# CAN_I2C.net
KiCad netlist of a schematic drawn in Altium Designer
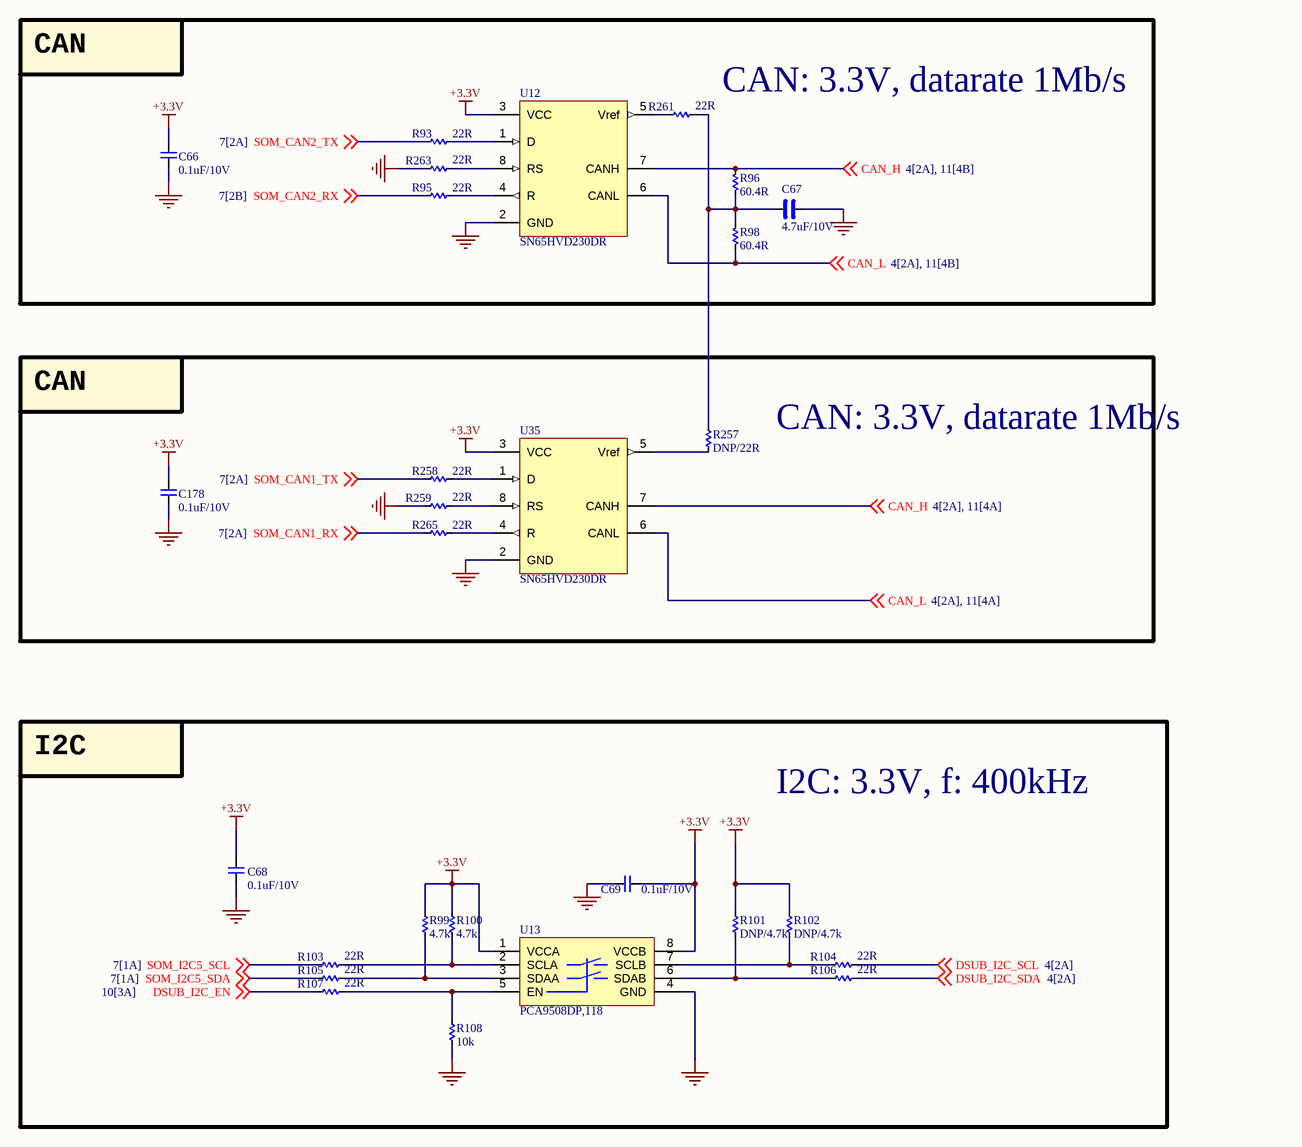
[diagram p0: CAN_I2C.SchDoc]

(export (version "E")
  (design (tool "Eeschema 10.0.6"))
  (components
    (comp (ref "C66")
      (value "0.1uF/10V")
      (footprint "CAP_C_1005X60")
      (description "CAP CHIP")
      (libsource (lib "LABLIB") (part "_CAP_C_2"))
    )
    (comp (ref "C67")
      (value "4.7uF/10V")
      (footprint "CAP_C_1608X80")
      (description "CAP CHIP High Value")
      (libsource (lib "LABLIB") (part "_CAP_C_High_2"))
    )
    (comp (ref "C68")
      (value "0.1uF/10V")
      (footprint "CAP_C_1005X60")
      (description "CAP CHIP")
      (libsource (lib "LABLIB") (part "_CAP_C_2"))
    )
    (comp (ref "C69")
      (value "0.1uF/10V")
      (footprint "CAP_C_1005X60")
      (description "CAP CHIP")
      (libsource (lib "LABLIB") (part "_CAP_C_2"))
    )
    (comp (ref "C178")
      (value "0.1uF/10V")
      (footprint "CAP_C_1005X60")
      (description "CAP CHIP")
      (libsource (lib "LABLIB") (part "_CAP_C_2"))
    )
    (comp (ref "R93")
      (value "22R")
      (footprint "RES_C_1005X40")
      (description "RES")
      (libsource (lib "LABLIB") (part "_RES_B_2"))
    )
    (comp (ref "R95")
      (value "22R")
      (footprint "RES_C_1005X40")
      (description "RES")
      (libsource (lib "LABLIB") (part "_RES_B_2"))
    )
    (comp (ref "R96")
      (value "60.4R")
      (footprint "RES_C_1005X40")
      (description "RES")
      (libsource (lib "LABLIB") (part "_RES_B_2"))
    )
    (comp (ref "R98")
      (value "60.4R")
      (footprint "RES_C_1005X40")
      (description "RES")
      (libsource (lib "LABLIB") (part "_RES_B_2"))
    )
    (comp (ref "R99")
      (value "4.7k")
      (footprint "RES_C_1005X40")
      (description "RES")
      (libsource (lib "LABLIB") (part "_RES_B_2"))
    )
    (comp (ref "R100")
      (value "4.7k")
      (footprint "RES_C_1005X40")
      (description "RES")
      (libsource (lib "LABLIB") (part "_RES_B_2"))
    )
    (comp (ref "R101")
      (value "DNP/4.7k")
      (footprint "RES_C_1005X40")
      (description "RES")
      (libsource (lib "LABLIB") (part "_RES_B_2"))
    )
    (comp (ref "R102")
      (value "DNP/4.7k")
      (footprint "RES_C_1005X40")
      (description "RES")
      (libsource (lib "LABLIB") (part "_RES_B_2"))
    )
    (comp (ref "R103")
      (value "22R")
      (footprint "RES_C_1005X40")
      (description "RES")
      (libsource (lib "LABLIB") (part "_RES_B_2"))
    )
    (comp (ref "R104")
      (value "22R")
      (footprint "RES_C_1005X40")
      (description "RES")
      (libsource (lib "LABLIB") (part "_RES_B_2"))
    )
    (comp (ref "R105")
      (value "22R")
      (footprint "RES_C_1005X40")
      (description "RES")
      (libsource (lib "LABLIB") (part "_RES_B_2"))
    )
    (comp (ref "R106")
      (value "22R")
      (footprint "RES_C_1005X40")
      (description "RES")
      (libsource (lib "LABLIB") (part "_RES_B_2"))
    )
    (comp (ref "R107")
      (value "22R")
      (footprint "RES_C_1005X40")
      (description "RES")
      (libsource (lib "LABLIB") (part "_RES_B_2"))
    )
    (comp (ref "R108")
      (value "10k")
      (footprint "RES_C_1005X40")
      (description "RES")
      (libsource (lib "LABLIB") (part "_RES_B_2"))
    )
    (comp (ref "R257")
      (value "DNP/22R")
      (footprint "RES_C_1005X40")
      (description "RES")
      (libsource (lib "LABLIB") (part "_RES_B_2"))
    )
    (comp (ref "R258")
      (value "22R")
      (footprint "RES_C_1005X40")
      (description "RES")
      (libsource (lib "LABLIB") (part "_RES_B_2"))
    )
    (comp (ref "R259")
      (value "22R")
      (footprint "RES_C_1005X40")
      (description "RES")
      (libsource (lib "LABLIB") (part "_RES_B_2"))
    )
    (comp (ref "R261")
      (value "22R")
      (footprint "RES_C_1005X40")
      (description "RES")
      (libsource (lib "LABLIB") (part "_RES_B_2"))
    )
    (comp (ref "R263")
      (value "22R")
      (footprint "RES_C_1005X40")
      (description "RES")
      (libsource (lib "LABLIB") (part "_RES_B_2"))
    )
    (comp (ref "R265")
      (value "22R")
      (footprint "RES_C_1005X40")
      (description "RES")
      (libsource (lib "LABLIB") (part "_RES_B_2"))
    )
    (comp (ref "U12")
      (value "SN65HVD230DR")
      (footprint "SOIC127P602X173-8N")
      (description "IC TRANSCEIVER HALF 1/1 8SOIC")
      (libsource (lib "LABLIB") (part "IC_CAN_SN65HVD230DR"))
    )
    (comp (ref "U13")
      (value "PCA9508DP,118")
      (footprint "TSOP8")
      (libsource (lib "EXP_HW_V3") (part "PCA9508DP,118"))
    )
    (comp (ref "U35")
      (value "SN65HVD230DR")
      (footprint "SOIC127P602X173-8N")
      (description "IC TRANSCEIVER HALF 1/1 8SOIC")
      (libsource (lib "LABLIB") (part "IC_CAN_SN65HVD230DR"))
    )
  )
  (nets
    (net (code "1") (name "+3.3V") (class "Default")
      (node (ref "C178") (pin "2") (pinfunction "2_2") (pintype "passive"))
      (node (ref "C66") (pin "2") (pinfunction "2_2") (pintype "passive"))
      (node (ref "C68") (pin "2") (pinfunction "2_2") (pintype "passive"))
      (node (ref "C69") (pin "1") (pinfunction "1_1") (pintype "passive"))
      (node (ref "R100") (pin "1") (pinfunction "1_1") (pintype "passive"))
      (node (ref "R101") (pin "1") (pinfunction "1_1") (pintype "passive"))
      (node (ref "R102") (pin "1") (pinfunction "1_1") (pintype "passive"))
      (node (ref "R99") (pin "1") (pinfunction "1_1") (pintype "passive"))
      (node (ref "U12") (pin "3") (pinfunction "VCC_3") (pintype "passive"))
      (node (ref "U13") (pin "1") (pinfunction "VCCA_1") (pintype "passive"))
      (node (ref "U13") (pin "8") (pinfunction "VCCB_8") (pintype "passive"))
      (node (ref "U35") (pin "3") (pinfunction "VCC_3") (pintype "passive"))
    )
    (net (code "2") (name "CAN_H") (class "Default")
      (node (ref "R96") (pin "2") (pinfunction "2_2") (pintype "passive"))
      (node (ref "U12") (pin "7") (pinfunction "CANH_7") (pintype "passive"))
      (node (ref "U35") (pin "7") (pinfunction "CANH_7") (pintype "passive"))
    )
    (net (code "3") (name "CAN_L") (class "Default")
      (node (ref "R98") (pin "1") (pinfunction "1_1") (pintype "passive"))
      (node (ref "U12") (pin "6") (pinfunction "CANL_6") (pintype "passive"))
      (node (ref "U35") (pin "6") (pinfunction "CANL_6") (pintype "passive"))
    )
    (net (code "4") (name "DSUB_I2C_EN") (class "Default")
      (node (ref "R107") (pin "2") (pinfunction "2_2") (pintype "passive"))
    )
    (net (code "5") (name "DSUB_I2C_SCL") (class "Default")
      (node (ref "R104") (pin "1") (pinfunction "1_1") (pintype "passive"))
    )
    (net (code "6") (name "DSUB_I2C_SDA") (class "Default")
      (node (ref "R106") (pin "1") (pinfunction "1_1") (pintype "passive"))
    )
    (net (code "7") (name "GND") (class "Default")
      (node (ref "C178") (pin "1") (pinfunction "1_1") (pintype "passive"))
      (node (ref "C66") (pin "1") (pinfunction "1_1") (pintype "passive"))
      (node (ref "C67") (pin "1") (pinfunction "1_1") (pintype "passive"))
      (node (ref "C68") (pin "1") (pinfunction "1_1") (pintype "passive"))
      (node (ref "C69") (pin "2") (pinfunction "2_2") (pintype "passive"))
      (node (ref "R108") (pin "1") (pinfunction "1_1") (pintype "passive"))
      (node (ref "R259") (pin "2") (pinfunction "2_2") (pintype "passive"))
      (node (ref "R263") (pin "2") (pinfunction "2_2") (pintype "passive"))
      (node (ref "U12") (pin "2") (pinfunction "GND_2") (pintype "passive"))
      (node (ref "U13") (pin "4") (pinfunction "GND_4") (pintype "passive"))
      (node (ref "U35") (pin "2") (pinfunction "GND_2") (pintype "passive"))
    )
    (net (code "8") (name "Net-(C67-Pad2)") (class "Default")
      (node (ref "C67") (pin "2") (pinfunction "2_2") (pintype "passive"))
      (node (ref "R257") (pin "1") (pinfunction "1_1") (pintype "passive"))
      (node (ref "R261") (pin "1") (pinfunction "1_1") (pintype "passive"))
      (node (ref "R96") (pin "1") (pinfunction "1_1") (pintype "passive"))
      (node (ref "R98") (pin "2") (pinfunction "2_2") (pintype "passive"))
    )
    (net (code "9") (name "Net-(U12-D)") (class "Default")
      (node (ref "R93") (pin "2") (pinfunction "2_2") (pintype "passive"))
      (node (ref "U12") (pin "1") (pinfunction "D_1") (pintype "input"))
    )
    (net (code "10") (name "Net-(U12-R)") (class "Default")
      (node (ref "R95") (pin "2") (pinfunction "2_2") (pintype "passive"))
      (node (ref "U12") (pin "4") (pinfunction "R_4") (pintype "output"))
    )
    (net (code "11") (name "Net-(U12-RS)") (class "Default")
      (node (ref "R263") (pin "1") (pinfunction "1_1") (pintype "passive"))
      (node (ref "U12") (pin "8") (pinfunction "RS_8") (pintype "input"))
    )
    (net (code "12") (name "Net-(U12-Vref)") (class "Default")
      (node (ref "R261") (pin "2") (pinfunction "2_2") (pintype "passive"))
      (node (ref "U12") (pin "5") (pinfunction "Vref_5") (pintype "output"))
    )
    (net (code "13") (name "Net-(U13-EN)") (class "Default")
      (node (ref "R107") (pin "1") (pinfunction "1_1") (pintype "passive"))
      (node (ref "R108") (pin "2") (pinfunction "2_2") (pintype "passive"))
      (node (ref "U13") (pin "5") (pinfunction "EN_5") (pintype "passive"))
    )
    (net (code "14") (name "Net-(U13-SCLA)") (class "Default")
      (node (ref "R100") (pin "2") (pinfunction "2_2") (pintype "passive"))
      (node (ref "R103") (pin "1") (pinfunction "1_1") (pintype "passive"))
      (node (ref "U13") (pin "2") (pinfunction "SCLA_2") (pintype "passive"))
    )
    (net (code "15") (name "Net-(U13-SCLB)") (class "Default")
      (node (ref "R102") (pin "2") (pinfunction "2_2") (pintype "passive"))
      (node (ref "R104") (pin "2") (pinfunction "2_2") (pintype "passive"))
      (node (ref "U13") (pin "7") (pinfunction "SCLB_7") (pintype "passive"))
    )
    (net (code "16") (name "Net-(U13-SDAA)") (class "Default")
      (node (ref "R105") (pin "1") (pinfunction "1_1") (pintype "passive"))
      (node (ref "R99") (pin "2") (pinfunction "2_2") (pintype "passive"))
      (node (ref "U13") (pin "3") (pinfunction "SDAA_3") (pintype "passive"))
    )
    (net (code "17") (name "Net-(U13-SDAB)") (class "Default")
      (node (ref "R101") (pin "2") (pinfunction "2_2") (pintype "passive"))
      (node (ref "R106") (pin "2") (pinfunction "2_2") (pintype "passive"))
      (node (ref "U13") (pin "6") (pinfunction "SDAB_6") (pintype "passive"))
    )
    (net (code "18") (name "Net-(U35-D)") (class "Default")
      (node (ref "R258") (pin "2") (pinfunction "2_2") (pintype "passive"))
      (node (ref "U35") (pin "1") (pinfunction "D_1") (pintype "input"))
    )
    (net (code "19") (name "Net-(U35-R)") (class "Default")
      (node (ref "R265") (pin "2") (pinfunction "2_2") (pintype "passive"))
      (node (ref "U35") (pin "4") (pinfunction "R_4") (pintype "output"))
    )
    (net (code "20") (name "Net-(U35-RS)") (class "Default")
      (node (ref "R259") (pin "1") (pinfunction "1_1") (pintype "passive"))
      (node (ref "U35") (pin "8") (pinfunction "RS_8") (pintype "input"))
    )
    (net (code "21") (name "Net-(U35-Vref)") (class "Default")
      (node (ref "R257") (pin "2") (pinfunction "2_2") (pintype "passive"))
      (node (ref "U35") (pin "5") (pinfunction "Vref_5") (pintype "output"))
    )
    (net (code "22") (name "SOM_CAN1_RX") (class "Default")
      (node (ref "R265") (pin "1") (pinfunction "1_1") (pintype "passive"))
    )
    (net (code "23") (name "SOM_CAN1_TX") (class "Default")
      (node (ref "R258") (pin "1") (pinfunction "1_1") (pintype "passive"))
    )
    (net (code "24") (name "SOM_CAN2_RX") (class "Default")
      (node (ref "R95") (pin "1") (pinfunction "1_1") (pintype "passive"))
    )
    (net (code "25") (name "SOM_CAN2_TX") (class "Default")
      (node (ref "R93") (pin "1") (pinfunction "1_1") (pintype "passive"))
    )
    (net (code "26") (name "SOM_I2C5_SCL") (class "Default")
      (node (ref "R103") (pin "2") (pinfunction "2_2") (pintype "passive"))
    )
    (net (code "27") (name "SOM_I2C5_SDA") (class "Default")
      (node (ref "R105") (pin "2") (pinfunction "2_2") (pintype "passive"))
    )
  )
)
